# control.net
KiCad netlist of a schematic drawn in Altium Designer
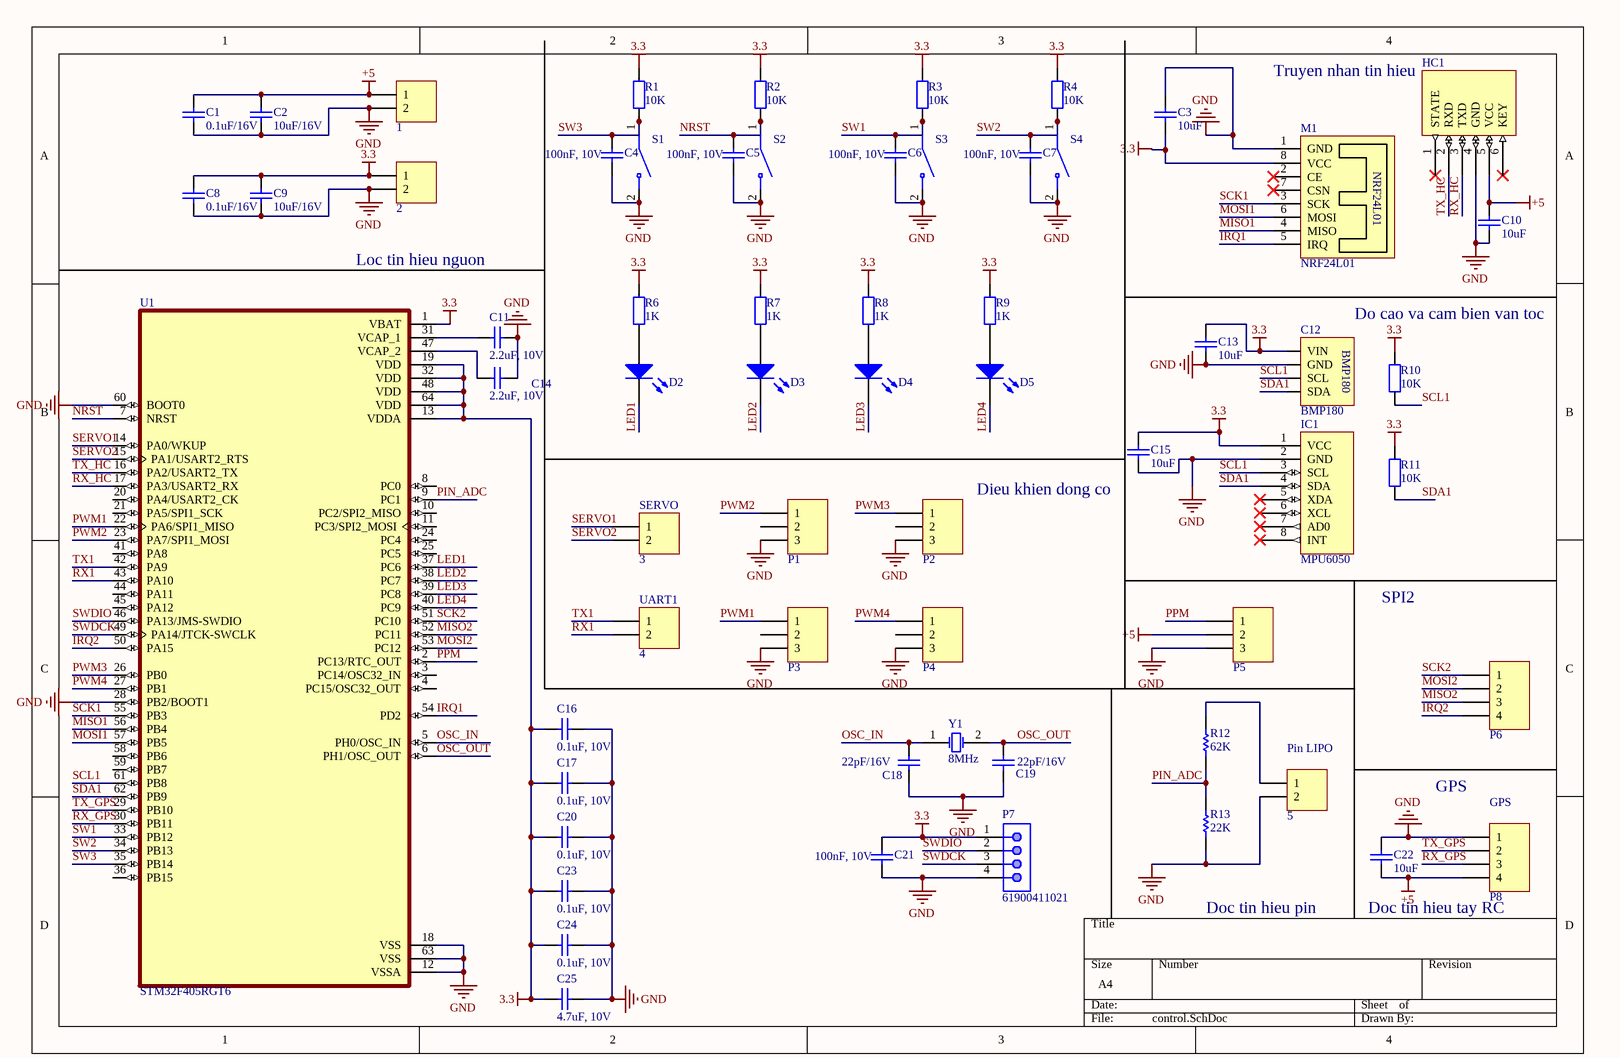
[diagram p0: control.SchDoc]

(export (version "E")
  (design (tool "Eeschema 10.0.6"))
  (components
    (comp (ref "1")
      (value "Header 2")
      (footprint "JP2")
      (description "Header, 2-Pin")
      (fields (field (name "PUBLISHER") "Altium Limited"))
      (libsource (lib "PIF_Library") (part "Header 2"))
    )
    (comp (ref "2")
      (value "Header 2")
      (footprint "JP2")
      (description "Header, 2-Pin")
      (fields (field (name "PUBLISHER") "Altium Limited"))
      (libsource (lib "PIF_Library") (part "Header 2"))
    )
    (comp (ref "3")
      (value "Header 2")
      (footprint "JP2")
      (description "Header, 2-Pin")
      (fields (field (name "PUBLISHER") "Altium Limited"))
      (libsource (lib "PIF_Library") (part "Header 2"))
    )
    (comp (ref "4")
      (value "Header 2")
      (footprint "JP2")
      (description "Header, 2-Pin")
      (fields (field (name "PUBLISHER") "Altium Limited"))
      (libsource (lib "PIF_Library") (part "Header 2"))
    )
    (comp (ref "5")
      (value "Header 2")
      (footprint "JP2")
      (description "Header, 2-Pin")
      (fields (field (name "PUBLISHER") "Altium Limited"))
      (libsource (lib "PIF_Library") (part "Header 2"))
    )
    (comp (ref "C1")
      (value "0.1uF/16V")
      (footprint "WCAP-CSMH_0603_L1.6W0.8H0.8_Reflow")
      (fields
        (field (name "MANUFACTURER PART NUMBER") "885342006001")
        (field (name "MANUFACTURER") "Wurth Elektronik")
      )
      (libsource (lib "Altium_WCAP-CSMH (rev22c)") (part "885342006001"))
    )
    (comp (ref "C2")
      (value "10uF/16V")
      (footprint "WCAP-CSMH_0603_L1.6W0.8H0.8_Reflow")
      (fields
        (field (name "MANUFACTURER PART NUMBER") "885342006001")
        (field (name "MANUFACTURER") "Wurth Elektronik")
      )
      (libsource (lib "Altium_WCAP-CSMH (rev22c)") (part "885342006001"))
    )
    (comp (ref "C3")
      (value "10uF")
      (footprint "WCAP-CSGP_0603_H=0.8mm_Reflow")
      (description "WCAP-CSGP Multilayer Ceramic Chip Capacitor, General Purpose, size 0603, NP0, 680pF, 10V")
      (fields
        (field (name "MANUFACTURER PART NUMBER") "885012006013")
        (field (name "MANUFACTURER") "Wurth Elektronik")
      )
      (libsource (lib "Altium_WCAP-CSGP (rev20a)") (part "885012006013"))
    )
    (comp (ref "C4")
      (value "100nF, 10V")
      (footprint "WCAP-CSGP_0603_H=0.8mm_Reflow")
      (description "WCAP-CSGP Multilayer Ceramic Chip Capacitor, General Purpose, size 0603, NP0, 680pF, 10V")
      (fields
        (field (name "MANUFACTURER PART NUMBER") "885012006013")
        (field (name "MANUFACTURER") "Wurth Elektronik")
      )
      (libsource (lib "Altium_WCAP-CSGP (rev20a)") (part "885012006013"))
    )
    (comp (ref "C5")
      (value "100nF, 10V")
      (footprint "WCAP-CSGP_0603_H=0.8mm_Reflow")
      (description "WCAP-CSGP Multilayer Ceramic Chip Capacitor, General Purpose, size 0603, NP0, 680pF, 10V")
      (fields
        (field (name "MANUFACTURER PART NUMBER") "885012006013")
        (field (name "MANUFACTURER") "Wurth Elektronik")
      )
      (libsource (lib "Altium_WCAP-CSGP (rev20a)") (part "885012006013"))
    )
    (comp (ref "C6")
      (value "100nF, 10V")
      (footprint "WCAP-CSGP_0603_H=0.8mm_Reflow")
      (description "WCAP-CSGP Multilayer Ceramic Chip Capacitor, General Purpose, size 0603, NP0, 680pF, 10V")
      (fields
        (field (name "MANUFACTURER PART NUMBER") "885012006013")
        (field (name "MANUFACTURER") "Wurth Elektronik")
      )
      (libsource (lib "Altium_WCAP-CSGP (rev20a)") (part "885012006013"))
    )
    (comp (ref "C7")
      (value "100nF, 10V")
      (footprint "WCAP-CSGP_0603_H=0.8mm_Reflow")
      (description "WCAP-CSGP Multilayer Ceramic Chip Capacitor, General Purpose, size 0603, NP0, 680pF, 10V")
      (fields
        (field (name "MANUFACTURER PART NUMBER") "885012006013")
        (field (name "MANUFACTURER") "Wurth Elektronik")
      )
      (libsource (lib "Altium_WCAP-CSGP (rev20a)") (part "885012006013"))
    )
    (comp (ref "C8")
      (value "0.1uF/16V")
      (footprint "WCAP-CSMH_0603_L1.6W0.8H0.8_Reflow")
      (fields
        (field (name "MANUFACTURER PART NUMBER") "885342006001")
        (field (name "MANUFACTURER") "Wurth Elektronik")
      )
      (libsource (lib "Altium_WCAP-CSMH (rev22c)") (part "885342006001"))
    )
    (comp (ref "C9")
      (value "10uF/16V")
      (footprint "WCAP-CSMH_0603_L1.6W0.8H0.8_Reflow")
      (fields
        (field (name "MANUFACTURER PART NUMBER") "885342006001")
        (field (name "MANUFACTURER") "Wurth Elektronik")
      )
      (libsource (lib "Altium_WCAP-CSMH (rev22c)") (part "885342006001"))
    )
    (comp (ref "C10")
      (value "10uF")
      (footprint "WCAP-CSGP_0603_H=0.8mm_Reflow")
      (description "WCAP-CSGP Multilayer Ceramic Chip Capacitor, General Purpose, size 0603, NP0, 680pF, 10V")
      (fields
        (field (name "MANUFACTURER PART NUMBER") "885012006013")
        (field (name "MANUFACTURER") "Wurth Elektronik")
      )
      (libsource (lib "Altium_WCAP-CSGP (rev20a)") (part "885012006013"))
    )
    (comp (ref "C11")
      (value "2.2uF, 10V")
      (footprint "WCAP-CSGP_0603_H=0.8mm_Reflow")
      (description "WCAP-CSGP Multilayer Ceramic Chip Capacitor, General Purpose, size 0603, NP0, 680pF, 10V")
      (fields
        (field (name "MANUFACTURER PART NUMBER") "885012006013")
        (field (name "MANUFACTURER") "Wurth Elektronik")
      )
      (libsource (lib "Altium_WCAP-CSGP (rev20a)") (part "885012006013"))
    )
    (comp (ref "C12")
      (value "BMP180")
      (footprint "JP4-C1T")
      (fields
        (field (name "MANUFACTURER") "Würth Elektronik eiSos GmbH")
        (field (name "PARTNO") "613004143121")
        (field (name "CREATED BY") "Karrer Zheng")
      )
      (libsource (lib "TechMT.VN_Lib_Project v2") (part "BMP180"))
    )
    (comp (ref "C13")
      (value "10uF")
      (footprint "WCAP-CSGP_0603_H=0.8mm_Reflow")
      (description "WCAP-CSGP Multilayer Ceramic Chip Capacitor, General Purpose, size 0603, NP0, 680pF, 10V")
      (fields
        (field (name "MANUFACTURER PART NUMBER") "885012006013")
        (field (name "MANUFACTURER") "Wurth Elektronik")
      )
      (libsource (lib "Altium_WCAP-CSGP (rev20a)") (part "885012006013"))
    )
    (comp (ref "C14")
      (value "2.2uF, 10V")
      (footprint "WCAP-CSGP_0603_H=0.8mm_Reflow")
      (description "WCAP-CSGP Multilayer Ceramic Chip Capacitor, General Purpose, size 0603, NP0, 680pF, 10V")
      (fields
        (field (name "MANUFACTURER PART NUMBER") "885012006013")
        (field (name "MANUFACTURER") "Wurth Elektronik")
      )
      (libsource (lib "Altium_WCAP-CSGP (rev20a)") (part "885012006013"))
    )
    (comp (ref "C15")
      (value "10uF")
      (footprint "WCAP-CSGP_0603_H=0.8mm_Reflow")
      (description "WCAP-CSGP Multilayer Ceramic Chip Capacitor, General Purpose, size 0603, NP0, 680pF, 10V")
      (fields
        (field (name "MANUFACTURER PART NUMBER") "885012006013")
        (field (name "MANUFACTURER") "Wurth Elektronik")
      )
      (libsource (lib "Altium_WCAP-CSGP (rev20a)") (part "885012006013"))
    )
    (comp (ref "C16")
      (value "0.1uF, 10V")
      (footprint "WCAP-CSGP_0603_H=0.8mm_Reflow")
      (description "WCAP-CSGP Multilayer Ceramic Chip Capacitor, General Purpose, size 0603, NP0, 680pF, 10V")
      (fields
        (field (name "MANUFACTURER PART NUMBER") "885012006013")
        (field (name "MANUFACTURER") "Wurth Elektronik")
      )
      (libsource (lib "Altium_WCAP-CSGP (rev20a)") (part "885012006013"))
    )
    (comp (ref "C17")
      (value "0.1uF, 10V")
      (footprint "WCAP-CSGP_0603_H=0.8mm_Reflow")
      (description "WCAP-CSGP Multilayer Ceramic Chip Capacitor, General Purpose, size 0603, NP0, 680pF, 10V")
      (fields
        (field (name "MANUFACTURER PART NUMBER") "885012006013")
        (field (name "MANUFACTURER") "Wurth Elektronik")
      )
      (libsource (lib "Altium_WCAP-CSGP (rev20a)") (part "885012006013"))
    )
    (comp (ref "C18")
      (value "22pF/16V")
      (footprint "WCAP-CSMH_0603_L1.6W0.8H0.8_Reflow")
      (fields
        (field (name "MANUFACTURER PART NUMBER") "885342006001")
        (field (name "MANUFACTURER") "Wurth Elektronik")
      )
      (libsource (lib "Altium_WCAP-CSMH (rev22c)") (part "885342006001"))
    )
    (comp (ref "C19")
      (value "22pF/16V")
      (footprint "WCAP-CSMH_0603_L1.6W0.8H0.8_Reflow")
      (fields
        (field (name "MANUFACTURER PART NUMBER") "885342006001")
        (field (name "MANUFACTURER") "Wurth Elektronik")
      )
      (libsource (lib "Altium_WCAP-CSMH (rev22c)") (part "885342006001"))
    )
    (comp (ref "C20")
      (value "0.1uF, 10V")
      (footprint "WCAP-CSGP_0603_H=0.8mm_Reflow")
      (description "WCAP-CSGP Multilayer Ceramic Chip Capacitor, General Purpose, size 0603, NP0, 680pF, 10V")
      (fields
        (field (name "MANUFACTURER PART NUMBER") "885012006013")
        (field (name "MANUFACTURER") "Wurth Elektronik")
      )
      (libsource (lib "Altium_WCAP-CSGP (rev20a)") (part "885012006013"))
    )
    (comp (ref "C21")
      (value "100nF, 10V")
      (footprint "WCAP-CSGP_0603_H=0.8mm_Reflow")
      (description "WCAP-CSGP Multilayer Ceramic Chip Capacitor, General Purpose, size 0603, NP0, 680pF, 10V")
      (fields
        (field (name "MANUFACTURER PART NUMBER") "885012006013")
        (field (name "MANUFACTURER") "Wurth Elektronik")
      )
      (libsource (lib "Altium_WCAP-CSGP (rev20a)") (part "885012006013"))
    )
    (comp (ref "C22")
      (value "10uF")
      (footprint "WCAP-CSGP_0603_H=0.8mm_Reflow")
      (description "WCAP-CSGP Multilayer Ceramic Chip Capacitor, General Purpose, size 0603, NP0, 680pF, 10V")
      (fields
        (field (name "MANUFACTURER PART NUMBER") "885012006013")
        (field (name "MANUFACTURER") "Wurth Elektronik")
      )
      (libsource (lib "Altium_WCAP-CSGP (rev20a)") (part "885012006013"))
    )
    (comp (ref "C23")
      (value "0.1uF, 10V")
      (footprint "WCAP-CSGP_0603_H=0.8mm_Reflow")
      (description "WCAP-CSGP Multilayer Ceramic Chip Capacitor, General Purpose, size 0603, NP0, 680pF, 10V")
      (fields
        (field (name "MANUFACTURER PART NUMBER") "885012006013")
        (field (name "MANUFACTURER") "Wurth Elektronik")
      )
      (libsource (lib "Altium_WCAP-CSGP (rev20a)") (part "885012006013"))
    )
    (comp (ref "C24")
      (value "0.1uF, 10V")
      (footprint "WCAP-CSGP_0603_H=0.8mm_Reflow")
      (description "WCAP-CSGP Multilayer Ceramic Chip Capacitor, General Purpose, size 0603, NP0, 680pF, 10V")
      (fields
        (field (name "MANUFACTURER PART NUMBER") "885012006013")
        (field (name "MANUFACTURER") "Wurth Elektronik")
      )
      (libsource (lib "Altium_WCAP-CSGP (rev20a)") (part "885012006013"))
    )
    (comp (ref "C25")
      (value "4.7uF, 10V")
      (footprint "WCAP-CSGP_0603_H=0.8mm_Reflow")
      (description "WCAP-CSGP Multilayer Ceramic Chip Capacitor, General Purpose, size 0603, NP0, 680pF, 10V")
      (fields
        (field (name "MANUFACTURER PART NUMBER") "885012006013")
        (field (name "MANUFACTURER") "Wurth Elektronik")
      )
      (libsource (lib "Altium_WCAP-CSGP (rev20a)") (part "885012006013"))
    )
    (comp (ref "D2")
      (value "LED SMD")
      (footprint "LED_0603_Blue")
      (description "LED")
      (libsource (lib "PIF_Library") (part "LED SMD"))
    )
    (comp (ref "D3")
      (value "LED SMD")
      (footprint "LED_0603_Blue")
      (description "LED")
      (libsource (lib "PIF_Library") (part "LED SMD"))
    )
    (comp (ref "D4")
      (value "LED SMD")
      (footprint "LED_0603_Blue")
      (description "LED")
      (libsource (lib "PIF_Library") (part "LED SMD"))
    )
    (comp (ref "D5")
      (value "LED SMD")
      (footprint "LED_0603_Blue")
      (description "LED")
      (libsource (lib "PIF_Library") (part "LED SMD"))
    )
    (comp (ref "HC1")
      (value "Module thu phát bluetooth HC-06")
      (footprint "hc-06")
      (description "CSR Bluetooth V2.0")
      (libsource (lib "TechMT.VN_Lib_Project v2") (part "HC-06"))
    )
    (comp (ref "IC1")
      (value "MPU6050")
      (footprint "MPU6050")
      (description "GY-521 6DOF IMU MPU6050\r\nTECHMT.VN")
      (libsource (lib "TechMT.VN_Lib_Project v2") (part "IMU MPU6050"))
    )
    (comp (ref "M1")
      (value "NRF24L01")
      (footprint "NRF24L01")
      (libsource (lib "TechMT.VN_Lib_Project v2") (part "NRF24L01"))
    )
    (comp (ref "P1")
      (value "Header 3")
      (footprint "JP3")
      (description "Header, 3-Pin")
      (fields (field (name "PUBLISHER") "Altium Limited"))
      (libsource (lib "PIF_Library") (part "Header 3"))
    )
    (comp (ref "P2")
      (value "Header 3")
      (footprint "JP3")
      (description "Header, 3-Pin")
      (fields (field (name "PUBLISHER") "Altium Limited"))
      (libsource (lib "PIF_Library") (part "Header 3"))
    )
    (comp (ref "P3")
      (value "Header 3")
      (footprint "JP3")
      (description "Header, 3-Pin")
      (fields (field (name "PUBLISHER") "Altium Limited"))
      (libsource (lib "PIF_Library") (part "Header 3"))
    )
    (comp (ref "P4")
      (value "Header 3")
      (footprint "JP3")
      (description "Header, 3-Pin")
      (fields (field (name "PUBLISHER") "Altium Limited"))
      (libsource (lib "PIF_Library") (part "Header 3"))
    )
    (comp (ref "P5")
      (value "Header 3")
      (footprint "JP3")
      (description "Header, 3-Pin")
      (fields (field (name "PUBLISHER") "Altium Limited"))
      (libsource (lib "PIF_Library") (part "Header 3"))
    )
    (comp (ref "P6")
      (value "Header 4")
      (footprint "JP4")
      (description "Header, 4-Pin")
      (fields (field (name "PUBLISHER") "Altium Limited"))
      (libsource (lib "PIF_Library") (part "Header 4"))
    )
    (comp (ref "P7")
      (value "61900411021")
      (footprint "61900411021")
      (description "WR-WTB THT Male Left Angled Bottom Locking Header, pitch 2.54mm, 4p")
      (fields (field (name "PUBLISHER") "Wurth Elektronik"))
      (libsource (lib "653008114822_Altium_WR-WTB_rev20a") (part "61900411021"))
    )
    (comp (ref "P8")
      (value "Header 4")
      (footprint "JP4")
      (description "Header, 4-Pin")
      (fields (field (name "PUBLISHER") "Altium Limited"))
      (libsource (lib "PIF_Library") (part "Header 4"))
    )
    (comp (ref "R1")
      (value "10K")
      (footprint "WRIS-KSKE_0603")
      (description "WRIS-KSKE SMT Thick Film Resistor, size 0603, 10Ohm, 0.25W")
      (fields
        (field (name "MANUFACTURER") "Wurth Elektronik")
        (field (name "MANUFACTURER PART NUMBER") "560050316012")
      )
      (libsource (lib "Altium_WRIS-KSKE (rev20a)") (part "560050316012"))
    )
    (comp (ref "R2")
      (value "10K")
      (footprint "WRIS-KSKE_0603")
      (description "WRIS-KSKE SMT Thick Film Resistor, size 0603, 10Ohm, 0.25W")
      (fields
        (field (name "MANUFACTURER") "Wurth Elektronik")
        (field (name "MANUFACTURER PART NUMBER") "560050316012")
      )
      (libsource (lib "Altium_WRIS-KSKE (rev20a)") (part "560050316012"))
    )
    (comp (ref "R3")
      (value "10K")
      (footprint "WRIS-KSKE_0603")
      (description "WRIS-KSKE SMT Thick Film Resistor, size 0603, 10Ohm, 0.25W")
      (fields
        (field (name "MANUFACTURER") "Wurth Elektronik")
        (field (name "MANUFACTURER PART NUMBER") "560050316012")
      )
      (libsource (lib "Altium_WRIS-KSKE (rev20a)") (part "560050316012"))
    )
    (comp (ref "R4")
      (value "10K")
      (footprint "WRIS-KSKE_0603")
      (description "WRIS-KSKE SMT Thick Film Resistor, size 0603, 10Ohm, 0.25W")
      (fields
        (field (name "MANUFACTURER") "Wurth Elektronik")
        (field (name "MANUFACTURER PART NUMBER") "560050316012")
      )
      (libsource (lib "Altium_WRIS-KSKE (rev20a)") (part "560050316012"))
    )
    (comp (ref "R6")
      (value "1K")
      (footprint "WRIS-KSKE_0603")
      (description "WRIS-KSKE SMT Thick Film Resistor, size 0603, 10Ohm, 0.25W")
      (fields
        (field (name "MANUFACTURER") "Wurth Elektronik")
        (field (name "MANUFACTURER PART NUMBER") "560050316012")
      )
      (libsource (lib "Altium_WRIS-KSKE (rev20a)") (part "560050316012"))
    )
    (comp (ref "R7")
      (value "1K")
      (footprint "WRIS-KSKE_0603")
      (description "WRIS-KSKE SMT Thick Film Resistor, size 0603, 10Ohm, 0.25W")
      (fields
        (field (name "MANUFACTURER") "Wurth Elektronik")
        (field (name "MANUFACTURER PART NUMBER") "560050316012")
      )
      (libsource (lib "Altium_WRIS-KSKE (rev20a)") (part "560050316012"))
    )
    (comp (ref "R8")
      (value "1K")
      (footprint "WRIS-KSKE_0603")
      (description "WRIS-KSKE SMT Thick Film Resistor, size 0603, 10Ohm, 0.25W")
      (fields
        (field (name "MANUFACTURER") "Wurth Elektronik")
        (field (name "MANUFACTURER PART NUMBER") "560050316012")
      )
      (libsource (lib "Altium_WRIS-KSKE (rev20a)") (part "560050316012"))
    )
    (comp (ref "R9")
      (value "1K")
      (footprint "WRIS-KSKE_0603")
      (description "WRIS-KSKE SMT Thick Film Resistor, size 0603, 10Ohm, 0.25W")
      (fields
        (field (name "MANUFACTURER") "Wurth Elektronik")
        (field (name "MANUFACTURER PART NUMBER") "560050316012")
      )
      (libsource (lib "Altium_WRIS-KSKE (rev20a)") (part "560050316012"))
    )
    (comp (ref "R10")
      (value "10K")
      (footprint "WRIS-KSKE_0603")
      (description "WRIS-KSKE SMT Thick Film Resistor, size 0603, 10Ohm, 0.25W")
      (fields
        (field (name "MANUFACTURER") "Wurth Elektronik")
        (field (name "MANUFACTURER PART NUMBER") "560050316012")
      )
      (libsource (lib "Altium_WRIS-KSKE (rev20a)") (part "560050316012"))
    )
    (comp (ref "R11")
      (value "10K")
      (footprint "WRIS-KSKE_0603")
      (description "WRIS-KSKE SMT Thick Film Resistor, size 0603, 10Ohm, 0.25W")
      (fields
        (field (name "MANUFACTURER") "Wurth Elektronik")
        (field (name "MANUFACTURER PART NUMBER") "560050316012")
      )
      (libsource (lib "Altium_WRIS-KSKE (rev20a)") (part "560050316012"))
    )
    (comp (ref "R12")
      (value "62K")
      (footprint "RES-SM-0805")
      (description "Resistor")
      (fields (field (name "Comment") "RESISTOR SMD"))
      (libsource (lib "PIF_Library") (part "RESISTOR SMD"))
    )
    (comp (ref "R13")
      (value "22K")
      (footprint "RES-SM-0805")
      (description "Resistor")
      (fields (field (name "Comment") "RESISTOR SMD"))
      (libsource (lib "PIF_Library") (part "RESISTOR SMD"))
    )
    (comp (ref "S1")
      (value "TS09-63-25-WT-160-SMT-TR")
      (footprint "SW_TS09-63-25-WT-160-SMT-TR")
      (libsource (lib "TS09-63-25-WT-160-SMT-TR") (part "TS09-63-25-WT-160-SMT-TR"))
    )
    (comp (ref "S2")
      (value "TS09-63-25-WT-160-SMT-TR")
      (footprint "SW_TS09-63-25-WT-160-SMT-TR")
      (libsource (lib "TS09-63-25-WT-160-SMT-TR") (part "TS09-63-25-WT-160-SMT-TR"))
    )
    (comp (ref "S3")
      (value "TS09-63-25-WT-160-SMT-TR")
      (footprint "SW_TS09-63-25-WT-160-SMT-TR")
      (libsource (lib "TS09-63-25-WT-160-SMT-TR") (part "TS09-63-25-WT-160-SMT-TR"))
    )
    (comp (ref "S4")
      (value "TS09-63-25-WT-160-SMT-TR")
      (footprint "SW_TS09-63-25-WT-160-SMT-TR")
      (libsource (lib "TS09-63-25-WT-160-SMT-TR") (part "TS09-63-25-WT-160-SMT-TR"))
    )
    (comp (ref "U1")
      (value "STM32F405RGT6")
      (footprint "QFP50P1200X1200X160-64N")
      (libsource (lib "STM32F405RGT6") (part "STM32F405RGT6"))
    )
    (comp (ref "Y1")
      (value "8MHz")
      (footprint "WE-XTAL_HC49/4H")
      (description "WE-XTAL Quartz Crystal, THT, HC49/4H, 8MHz, +/-30ppm")
      (fields
        (field (name "MANUFACTURER PART NUMBER") "830003156B")
        (field (name "MANUFACTURER") "Wurth Elektronik")
      )
      (libsource (lib "Altium_WE-XTAL (rev20c)") (part "830003156B"))
    )
  )
  (nets
    (net (code "1") (name "+5") (class "Default")
      (node (ref "1") (pin "1") (pinfunction "1_1") (pintype "passive"))
      (node (ref "C1") (pin "2") (pinfunction "2_2") (pintype "passive"))
      (node (ref "C10") (pin "1") (pinfunction "1_1") (pintype "passive"))
      (node (ref "C2") (pin "2") (pinfunction "2_2") (pintype "passive"))
      (node (ref "C22") (pin "2") (pinfunction "2_2") (pintype "passive"))
      (node (ref "HC1") (pin "5") (pinfunction "VCC_5") (pintype "bidirectional"))
      (node (ref "P5") (pin "2") (pinfunction "2_2") (pintype "passive"))
      (node (ref "P8") (pin "4") (pinfunction "4_4") (pintype "passive"))
    )
    (net (code "2") (name "/IRQ1") (class "Default")
      (node (ref "M1") (pin "5") (pinfunction "IRQ_5") (pintype "passive"))
      (node (ref "U1") (pin "54") (pinfunction "PD2_54") (pintype "bidirectional"))
    )
    (net (code "3") (name "/IRQ2") (class "Default")
      (node (ref "P6") (pin "4") (pinfunction "4_4") (pintype "passive"))
      (node (ref "U1") (pin "50") (pinfunction "PA15_50") (pintype "bidirectional"))
    )
    (net (code "4") (name "/LED1") (class "Default")
      (node (ref "D2") (pin "2") (pinfunction "K_2") (pintype "passive"))
      (node (ref "U1") (pin "37") (pinfunction "PC6_37") (pintype "bidirectional"))
    )
    (net (code "5") (name "/LED2") (class "Default")
      (node (ref "D3") (pin "2") (pinfunction "K_2") (pintype "passive"))
      (node (ref "U1") (pin "38") (pinfunction "PC7_38") (pintype "bidirectional"))
    )
    (net (code "6") (name "/LED3") (class "Default")
      (node (ref "D4") (pin "2") (pinfunction "K_2") (pintype "passive"))
      (node (ref "U1") (pin "39") (pinfunction "PC8_39") (pintype "bidirectional"))
    )
    (net (code "7") (name "/LED4") (class "Default")
      (node (ref "D5") (pin "2") (pinfunction "K_2") (pintype "passive"))
      (node (ref "U1") (pin "40") (pinfunction "PC9_40") (pintype "bidirectional"))
    )
    (net (code "8") (name "/MISO1") (class "Default")
      (node (ref "M1") (pin "4") (pinfunction "MISO_4") (pintype "passive"))
      (node (ref "U1") (pin "56") (pinfunction "PB4_56") (pintype "bidirectional"))
    )
    (net (code "9") (name "/MISO2") (class "Default")
      (node (ref "P6") (pin "3") (pinfunction "3_3") (pintype "passive"))
      (node (ref "U1") (pin "52") (pinfunction "PC11_52") (pintype "bidirectional"))
    )
    (net (code "10") (name "/MOSI1") (class "Default")
      (node (ref "M1") (pin "6") (pinfunction "MOSI_6") (pintype "passive"))
      (node (ref "U1") (pin "57") (pinfunction "PB5_57") (pintype "bidirectional"))
    )
    (net (code "11") (name "/MOSI2") (class "Default")
      (node (ref "P6") (pin "2") (pinfunction "2_2") (pintype "passive"))
      (node (ref "U1") (pin "53") (pinfunction "PC12_53") (pintype "bidirectional"))
    )
    (net (code "12") (name "/NRST") (class "Default")
      (node (ref "C5") (pin "2") (pinfunction "2_2") (pintype "passive"))
      (node (ref "R2") (pin "1") (pinfunction "1_1") (pintype "passive"))
      (node (ref "S2") (pin "1") (pinfunction "1_1") (pintype "passive"))
      (node (ref "U1") (pin "7") (pinfunction "NRST_7") (pintype "bidirectional"))
    )
    (net (code "13") (name "/OSC_IN") (class "Default")
      (node (ref "C18") (pin "2") (pinfunction "2_2") (pintype "passive"))
      (node (ref "U1") (pin "5") (pinfunction "PH0/OSC_IN_5") (pintype "bidirectional"))
      (node (ref "Y1") (pin "1") (pinfunction "OSC1_1") (pintype "passive"))
    )
    (net (code "14") (name "/OSC_OUT") (class "Default")
      (node (ref "C19") (pin "2") (pinfunction "2_2") (pintype "passive"))
      (node (ref "U1") (pin "6") (pinfunction "PH1/OSC_OUT_6") (pintype "bidirectional"))
      (node (ref "Y1") (pin "2") (pinfunction "OSC2_2") (pintype "passive"))
    )
    (net (code "15") (name "/PIN_ADC") (class "Default")
      (node (ref "R12") (pin "1") (pinfunction "1_1") (pintype "passive"))
      (node (ref "R13") (pin "2") (pinfunction "2_2") (pintype "passive"))
      (node (ref "U1") (pin "9") (pinfunction "PC1_9") (pintype "bidirectional"))
    )
    (net (code "16") (name "/PPM") (class "Default")
      (node (ref "P5") (pin "1") (pinfunction "1_1") (pintype "passive"))
      (node (ref "U1") (pin "2") (pinfunction "PC13/RTC_OUT_2") (pintype "bidirectional"))
    )
    (net (code "17") (name "/PWM1") (class "Default")
      (node (ref "P3") (pin "1") (pinfunction "1_1") (pintype "passive"))
      (node (ref "U1") (pin "22") (pinfunction "PA6/SPI1_MISO_22") (pintype "bidirectional"))
    )
    (net (code "18") (name "/PWM2") (class "Default")
      (node (ref "P1") (pin "1") (pinfunction "1_1") (pintype "passive"))
      (node (ref "U1") (pin "23") (pinfunction "PA7/SPI1_MOSI_23") (pintype "bidirectional"))
    )
    (net (code "19") (name "/PWM3") (class "Default")
      (node (ref "P2") (pin "1") (pinfunction "1_1") (pintype "passive"))
      (node (ref "U1") (pin "26") (pinfunction "PB0_26") (pintype "bidirectional"))
    )
    (net (code "20") (name "/PWM4") (class "Default")
      (node (ref "P4") (pin "1") (pinfunction "1_1") (pintype "passive"))
      (node (ref "U1") (pin "27") (pinfunction "PB1_27") (pintype "bidirectional"))
    )
    (net (code "21") (name "/RX1") (class "Default")
      (node (ref "4") (pin "2") (pinfunction "2_2") (pintype "passive"))
      (node (ref "U1") (pin "43") (pinfunction "PA10_43") (pintype "bidirectional"))
    )
    (net (code "22") (name "/RX_GPS") (class "Default")
      (node (ref "P8") (pin "3") (pinfunction "3_3") (pintype "passive"))
      (node (ref "U1") (pin "30") (pinfunction "PB11_30") (pintype "bidirectional"))
    )
    (net (code "23") (name "/RX_HC") (class "Default")
      (node (ref "HC1") (pin "3") (pinfunction "TXD_3") (pintype "bidirectional"))
      (node (ref "U1") (pin "17") (pinfunction "PA3/USART2_RX_17") (pintype "bidirectional"))
    )
    (net (code "24") (name "/SCK1") (class "Default")
      (node (ref "M1") (pin "3") (pinfunction "SCK_3") (pintype "passive"))
      (node (ref "U1") (pin "55") (pinfunction "PB3_55") (pintype "bidirectional"))
    )
    (net (code "25") (name "/SCK2") (class "Default")
      (node (ref "P6") (pin "1") (pinfunction "1_1") (pintype "passive"))
      (node (ref "U1") (pin "51") (pinfunction "PC10_51") (pintype "bidirectional"))
    )
    (net (code "26") (name "/SCL1") (class "Default")
      (node (ref "C12") (pin "3") (pinfunction "SCL_3") (pintype "passive"))
      (node (ref "IC1") (pin "3") (pinfunction "SCL_3") (pintype "bidirectional"))
      (node (ref "R10") (pin "1") (pinfunction "1_1") (pintype "passive"))
      (node (ref "U1") (pin "61") (pinfunction "PB8_61") (pintype "bidirectional"))
    )
    (net (code "27") (name "/SDA1") (class "Default")
      (node (ref "C12") (pin "4") (pinfunction "SDA_4") (pintype "passive"))
      (node (ref "IC1") (pin "4") (pinfunction "SDA_4") (pintype "bidirectional"))
      (node (ref "R11") (pin "1") (pinfunction "1_1") (pintype "passive"))
      (node (ref "U1") (pin "62") (pinfunction "PB9_62") (pintype "bidirectional"))
    )
    (net (code "28") (name "/SERVO1") (class "Default")
      (node (ref "3") (pin "1") (pinfunction "1_1") (pintype "passive"))
      (node (ref "U1") (pin "14") (pinfunction "PA0/WKUP_14") (pintype "bidirectional"))
    )
    (net (code "29") (name "/SERVO2") (class "Default")
      (node (ref "3") (pin "2") (pinfunction "2_2") (pintype "passive"))
      (node (ref "U1") (pin "15") (pinfunction "PA1/USART2_RTS_15") (pintype "bidirectional"))
    )
    (net (code "30") (name "/SW1") (class "Default")
      (node (ref "C6") (pin "2") (pinfunction "2_2") (pintype "passive"))
      (node (ref "R3") (pin "1") (pinfunction "1_1") (pintype "passive"))
      (node (ref "S3") (pin "1") (pinfunction "1_1") (pintype "passive"))
      (node (ref "U1") (pin "33") (pinfunction "PB12_33") (pintype "bidirectional"))
    )
    (net (code "31") (name "/SW2") (class "Default")
      (node (ref "C7") (pin "2") (pinfunction "2_2") (pintype "passive"))
      (node (ref "R4") (pin "1") (pinfunction "1_1") (pintype "passive"))
      (node (ref "S4") (pin "1") (pinfunction "1_1") (pintype "passive"))
      (node (ref "U1") (pin "34") (pinfunction "PB13_34") (pintype "bidirectional"))
    )
    (net (code "32") (name "/SW3") (class "Default")
      (node (ref "C4") (pin "2") (pinfunction "2_2") (pintype "passive"))
      (node (ref "R1") (pin "1") (pinfunction "1_1") (pintype "passive"))
      (node (ref "S1") (pin "1") (pinfunction "1_1") (pintype "passive"))
      (node (ref "U1") (pin "35") (pinfunction "PB14_35") (pintype "bidirectional"))
    )
    (net (code "33") (name "/SWDCK") (class "Default")
      (node (ref "P7") (pin "3") (pinfunction "3_3") (pintype "passive"))
      (node (ref "U1") (pin "49") (pinfunction "PA14/JTCK-SWCLK_49") (pintype "bidirectional"))
    )
    (net (code "34") (name "/SWDIO") (class "Default")
      (node (ref "P7") (pin "2") (pinfunction "2_2") (pintype "passive"))
      (node (ref "U1") (pin "46") (pinfunction "PA13/JMS-SWDIO_46") (pintype "bidirectional"))
    )
    (net (code "35") (name "/TX1") (class "Default")
      (node (ref "4") (pin "1") (pinfunction "1_1") (pintype "passive"))
      (node (ref "U1") (pin "42") (pinfunction "PA9_42") (pintype "bidirectional"))
    )
    (net (code "36") (name "/TX_GPS") (class "Default")
      (node (ref "P8") (pin "2") (pinfunction "2_2") (pintype "passive"))
      (node (ref "U1") (pin "29") (pinfunction "PB10_29") (pintype "bidirectional"))
    )
    (net (code "37") (name "/TX_HC") (class "Default")
      (node (ref "HC1") (pin "2") (pinfunction "RXD_2") (pintype "bidirectional"))
      (node (ref "U1") (pin "16") (pinfunction "PA2/USART2_TX_16") (pintype "bidirectional"))
    )
    (net (code "38") (name "3.3") (class "Default")
      (node (ref "2") (pin "1") (pinfunction "1_1") (pintype "passive"))
      (node (ref "C12") (pin "1") (pinfunction "VIN_1") (pintype "passive"))
      (node (ref "C13") (pin "1") (pinfunction "1_1") (pintype "passive"))
      (node (ref "C15") (pin "1") (pinfunction "1_1") (pintype "passive"))
      (node (ref "C16") (pin "2") (pinfunction "2_2") (pintype "passive"))
      (node (ref "C17") (pin "2") (pinfunction "2_2") (pintype "passive"))
      (node (ref "C20") (pin "2") (pinfunction "2_2") (pintype "passive"))
      (node (ref "C21") (pin "2") (pinfunction "2_2") (pintype "passive"))
      (node (ref "C23") (pin "2") (pinfunction "2_2") (pintype "passive"))
      (node (ref "C24") (pin "2") (pinfunction "2_2") (pintype "passive"))
      (node (ref "C25") (pin "2") (pinfunction "2_2") (pintype "passive"))
      (node (ref "C3") (pin "2") (pinfunction "2_2") (pintype "passive"))
      (node (ref "C8") (pin "2") (pinfunction "2_2") (pintype "passive"))
      (node (ref "C9") (pin "2") (pinfunction "2_2") (pintype "passive"))
      (node (ref "IC1") (pin "1") (pinfunction "VCC_1") (pintype "power_in"))
      (node (ref "M1") (pin "8") (pinfunction "VCC_8") (pintype "passive"))
      (node (ref "P7") (pin "1") (pinfunction "1_1") (pintype "passive"))
      (node (ref "R1") (pin "2") (pinfunction "2_2") (pintype "passive"))
      (node (ref "R10") (pin "2") (pinfunction "2_2") (pintype "passive"))
      (node (ref "R11") (pin "2") (pinfunction "2_2") (pintype "passive"))
      (node (ref "R2") (pin "2") (pinfunction "2_2") (pintype "passive"))
      (node (ref "R3") (pin "2") (pinfunction "2_2") (pintype "passive"))
      (node (ref "R4") (pin "2") (pinfunction "2_2") (pintype "passive"))
      (node (ref "R6") (pin "2") (pinfunction "2_2") (pintype "passive"))
      (node (ref "R7") (pin "2") (pinfunction "2_2") (pintype "passive"))
      (node (ref "R8") (pin "2") (pinfunction "2_2") (pintype "passive"))
      (node (ref "R9") (pin "2") (pinfunction "2_2") (pintype "passive"))
      (node (ref "U1") (pin "1") (pinfunction "VBAT_1") (pintype "power_in"))
      (node (ref "U1") (pin "13") (pinfunction "VDDA_13") (pintype "power_in"))
      (node (ref "U1") (pin "19") (pinfunction "VDD_19") (pintype "power_in"))
      (node (ref "U1") (pin "32") (pinfunction "VDD_32") (pintype "power_in"))
      (node (ref "U1") (pin "48") (pinfunction "VDD_48") (pintype "power_in"))
      (node (ref "U1") (pin "64") (pinfunction "VDD_64") (pintype "power_in"))
    )
    (net (code "39") (name "GND") (class "Default")
      (node (ref "1") (pin "2") (pinfunction "2_2") (pintype "passive"))
      (node (ref "2") (pin "2") (pinfunction "2_2") (pintype "passive"))
      (node (ref "5") (pin "2") (pinfunction "2_2") (pintype "passive"))
      (node (ref "C1") (pin "1") (pinfunction "1_1") (pintype "passive"))
      (node (ref "C10") (pin "2") (pinfunction "2_2") (pintype "passive"))
      (node (ref "C11") (pin "2") (pinfunction "2_2") (pintype "passive"))
      (node (ref "C12") (pin "2") (pinfunction "GND_2") (pintype "passive"))
      (node (ref "C13") (pin "2") (pinfunction "2_2") (pintype "passive"))
      (node (ref "C14") (pin "2") (pinfunction "2_2") (pintype "passive"))
      (node (ref "C15") (pin "2") (pinfunction "2_2") (pintype "passive"))
      (node (ref "C16") (pin "1") (pinfunction "1_1") (pintype "passive"))
      (node (ref "C17") (pin "1") (pinfunction "1_1") (pintype "passive"))
      (node (ref "C18") (pin "1") (pinfunction "1_1") (pintype "passive"))
      (node (ref "C19") (pin "1") (pinfunction "1_1") (pintype "passive"))
      (node (ref "C2") (pin "1") (pinfunction "1_1") (pintype "passive"))
      (node (ref "C20") (pin "1") (pinfunction "1_1") (pintype "passive"))
      (node (ref "C21") (pin "1") (pinfunction "1_1") (pintype "passive"))
      (node (ref "C22") (pin "1") (pinfunction "1_1") (pintype "passive"))
      (node (ref "C23") (pin "1") (pinfunction "1_1") (pintype "passive"))
      (node (ref "C24") (pin "1") (pinfunction "1_1") (pintype "passive"))
      (node (ref "C25") (pin "1") (pinfunction "1_1") (pintype "passive"))
      (node (ref "C3") (pin "1") (pinfunction "1_1") (pintype "passive"))
      (node (ref "C4") (pin "1") (pinfunction "1_1") (pintype "passive"))
      (node (ref "C5") (pin "1") (pinfunction "1_1") (pintype "passive"))
      (node (ref "C6") (pin "1") (pinfunction "1_1") (pintype "passive"))
      (node (ref "C7") (pin "1") (pinfunction "1_1") (pintype "passive"))
      (node (ref "C8") (pin "1") (pinfunction "1_1") (pintype "passive"))
      (node (ref "C9") (pin "1") (pinfunction "1_1") (pintype "passive"))
      (node (ref "HC1") (pin "4") (pinfunction "GND_4") (pintype "bidirectional"))
      (node (ref "IC1") (pin "2") (pinfunction "GND_2") (pintype "power_in"))
      (node (ref "M1") (pin "1") (pinfunction "GND_1") (pintype "passive"))
      (node (ref "P1") (pin "3") (pinfunction "3_3") (pintype "passive"))
      (node (ref "P2") (pin "3") (pinfunction "3_3") (pintype "passive"))
      (node (ref "P3") (pin "3") (pinfunction "3_3") (pintype "passive"))
      (node (ref "P4") (pin "3") (pinfunction "3_3") (pintype "passive"))
      (node (ref "P5") (pin "3") (pinfunction "3_3") (pintype "passive"))
      (node (ref "P7") (pin "4") (pinfunction "4_4") (pintype "passive"))
      (node (ref "P8") (pin "1") (pinfunction "1_1") (pintype "passive"))
      (node (ref "R13") (pin "1") (pinfunction "1_1") (pintype "passive"))
      (node (ref "S1") (pin "2") (pinfunction "2_2") (pintype "passive"))
      (node (ref "S2") (pin "2") (pinfunction "2_2") (pintype "passive"))
      (node (ref "S3") (pin "2") (pinfunction "2_2") (pintype "passive"))
      (node (ref "S4") (pin "2") (pinfunction "2_2") (pintype "passive"))
      (node (ref "U1") (pin "12") (pinfunction "VSSA_12") (pintype "power_in"))
      (node (ref "U1") (pin "18") (pinfunction "VSS_18") (pintype "power_in"))
      (node (ref "U1") (pin "28") (pinfunction "PB2/BOOT1_28") (pintype "bidirectional"))
      (node (ref "U1") (pin "60") (pinfunction "BOOT0_60") (pintype "bidirectional"))
      (node (ref "U1") (pin "63") (pinfunction "VSS_63") (pintype "power_in"))
    )
    (net (code "40") (name "Net-(5-Pad1)") (class "Default")
      (node (ref "5") (pin "1") (pinfunction "1_1") (pintype "passive"))
      (node (ref "R12") (pin "2") (pinfunction "2_2") (pintype "passive"))
    )
    (net (code "41") (name "Net-(D2-A)") (class "Default")
      (node (ref "D2") (pin "1") (pinfunction "A_1") (pintype "passive"))
      (node (ref "R6") (pin "1") (pinfunction "1_1") (pintype "passive"))
    )
    (net (code "42") (name "Net-(D3-A)") (class "Default")
      (node (ref "D3") (pin "1") (pinfunction "A_1") (pintype "passive"))
      (node (ref "R7") (pin "1") (pinfunction "1_1") (pintype "passive"))
    )
    (net (code "43") (name "Net-(D4-A)") (class "Default")
      (node (ref "D4") (pin "1") (pinfunction "A_1") (pintype "passive"))
      (node (ref "R8") (pin "1") (pinfunction "1_1") (pintype "passive"))
    )
    (net (code "44") (name "Net-(D5-A)") (class "Default")
      (node (ref "D5") (pin "1") (pinfunction "A_1") (pintype "passive"))
      (node (ref "R9") (pin "1") (pinfunction "1_1") (pintype "passive"))
    )
    (net (code "45") (name "Net-(U1-VCAP_1)") (class "Default")
      (node (ref "C11") (pin "1") (pinfunction "1_1") (pintype "passive"))
      (node (ref "U1") (pin "31") (pinfunction "VCAP_1_31") (pintype "power_in"))
    )
    (net (code "46") (name "Net-(U1-VCAP_2)") (class "Default")
      (node (ref "C14") (pin "1") (pinfunction "1_1") (pintype "passive"))
      (node (ref "U1") (pin "47") (pinfunction "VCAP_2_47") (pintype "power_in"))
    )
    (net (code "47") (name "unconnected-(HC1-KEY-Pad6)") (class "Default")
      (node (ref "HC1") (pin "6") (pinfunction "KEY_6") (pintype "input+no_connect"))
    )
    (net (code "48") (name "unconnected-(HC1-STATE-Pad1)") (class "Default")
      (node (ref "HC1") (pin "1") (pinfunction "STATE_1") (pintype "output+no_connect"))
    )
    (net (code "49") (name "unconnected-(IC1-AD0-Pad7)") (class "Default")
      (node (ref "IC1") (pin "7") (pinfunction "AD0_7") (pintype "output+no_connect"))
    )
    (net (code "50") (name "unconnected-(IC1-INT-Pad8)") (class "Default")
      (node (ref "IC1") (pin "8") (pinfunction "INT_8") (pintype "output+no_connect"))
    )
    (net (code "51") (name "unconnected-(IC1-XCL-Pad6)") (class "Default")
      (node (ref "IC1") (pin "6") (pinfunction "XCL_6") (pintype "bidirectional+no_connect"))
    )
    (net (code "52") (name "unconnected-(IC1-XDA-Pad5)") (class "Default")
      (node (ref "IC1") (pin "5") (pinfunction "XDA_5") (pintype "bidirectional+no_connect"))
    )
    (net (code "53") (name "unconnected-(M1-CE-Pad2)") (class "Default")
      (node (ref "M1") (pin "2") (pinfunction "CE_2") (pintype "passive+no_connect"))
    )
    (net (code "54") (name "unconnected-(M1-CSN-Pad7)") (class "Default")
      (node (ref "M1") (pin "7") (pinfunction "CSN_7") (pintype "passive+no_connect"))
    )
    (net (code "55") (name "unconnected-(P1-Pad2)") (class "Default")
      (node (ref "P1") (pin "2") (pinfunction "2_2") (pintype "passive"))
    )
    (net (code "56") (name "unconnected-(P2-Pad2)") (class "Default")
      (node (ref "P2") (pin "2") (pinfunction "2_2") (pintype "passive"))
    )
    (net (code "57") (name "unconnected-(P3-Pad2)") (class "Default")
      (node (ref "P3") (pin "2") (pinfunction "2_2") (pintype "passive"))
    )
    (net (code "58") (name "unconnected-(P4-Pad2)") (class "Default")
      (node (ref "P4") (pin "2") (pinfunction "2_2") (pintype "passive"))
    )
    (net (code "59") (name "unconnected-(U1-PA4{slash}USART2_CK-Pad20)") (class "Default")
      (node (ref "U1") (pin "20") (pinfunction "PA4/USART2_CK_20") (pintype "bidirectional"))
    )
    (net (code "60") (name "unconnected-(U1-PA5{slash}SPI1_SCK-Pad21)") (class "Default")
      (node (ref "U1") (pin "21") (pinfunction "PA5/SPI1_SCK_21") (pintype "bidirectional"))
    )
    (net (code "61") (name "unconnected-(U1-PA8-Pad41)") (class "Default")
      (node (ref "U1") (pin "41") (pinfunction "PA8_41") (pintype "bidirectional"))
    )
    (net (code "62") (name "unconnected-(U1-PA11-Pad44)") (class "Default")
      (node (ref "U1") (pin "44") (pinfunction "PA11_44") (pintype "bidirectional"))
    )
    (net (code "63") (name "unconnected-(U1-PA12-Pad45)") (class "Default")
      (node (ref "U1") (pin "45") (pinfunction "PA12_45") (pintype "bidirectional"))
    )
    (net (code "64") (name "unconnected-(U1-PB6-Pad58)") (class "Default")
      (node (ref "U1") (pin "58") (pinfunction "PB6_58") (pintype "bidirectional"))
    )
    (net (code "65") (name "unconnected-(U1-PB7-Pad59)") (class "Default")
      (node (ref "U1") (pin "59") (pinfunction "PB7_59") (pintype "bidirectional"))
    )
    (net (code "66") (name "unconnected-(U1-PB15-Pad36)") (class "Default")
      (node (ref "U1") (pin "36") (pinfunction "PB15_36") (pintype "bidirectional"))
    )
    (net (code "67") (name "unconnected-(U1-PC0-Pad8)") (class "Default")
      (node (ref "U1") (pin "8") (pinfunction "PC0_8") (pintype "bidirectional"))
    )
    (net (code "68") (name "unconnected-(U1-PC2{slash}SPI2_MISO-Pad10)") (class "Default")
      (node (ref "U1") (pin "10") (pinfunction "PC2/SPI2_MISO_10") (pintype "bidirectional"))
    )
    (net (code "69") (name "unconnected-(U1-PC3{slash}SPI2_MOSI-Pad11)") (class "Default")
      (node (ref "U1") (pin "11") (pinfunction "PC3/SPI2_MOSI_11") (pintype "bidirectional"))
    )
    (net (code "70") (name "unconnected-(U1-PC4-Pad24)") (class "Default")
      (node (ref "U1") (pin "24") (pinfunction "PC4_24") (pintype "bidirectional"))
    )
    (net (code "71") (name "unconnected-(U1-PC5-Pad25)") (class "Default")
      (node (ref "U1") (pin "25") (pinfunction "PC5_25") (pintype "bidirectional"))
    )
    (net (code "72") (name "unconnected-(U1-PC14{slash}OSC32_IN-Pad3)") (class "Default")
      (node (ref "U1") (pin "3") (pinfunction "PC14/OSC32_IN_3") (pintype "bidirectional"))
    )
    (net (code "73") (name "unconnected-(U1-PC15{slash}OSC32_OUT-Pad4)") (class "Default")
      (node (ref "U1") (pin "4") (pinfunction "PC15/OSC32_OUT_4") (pintype "bidirectional"))
    )
  )
)
